# rfid_reader.net
KiCad netlist of a schematic drawn in Altium Designer
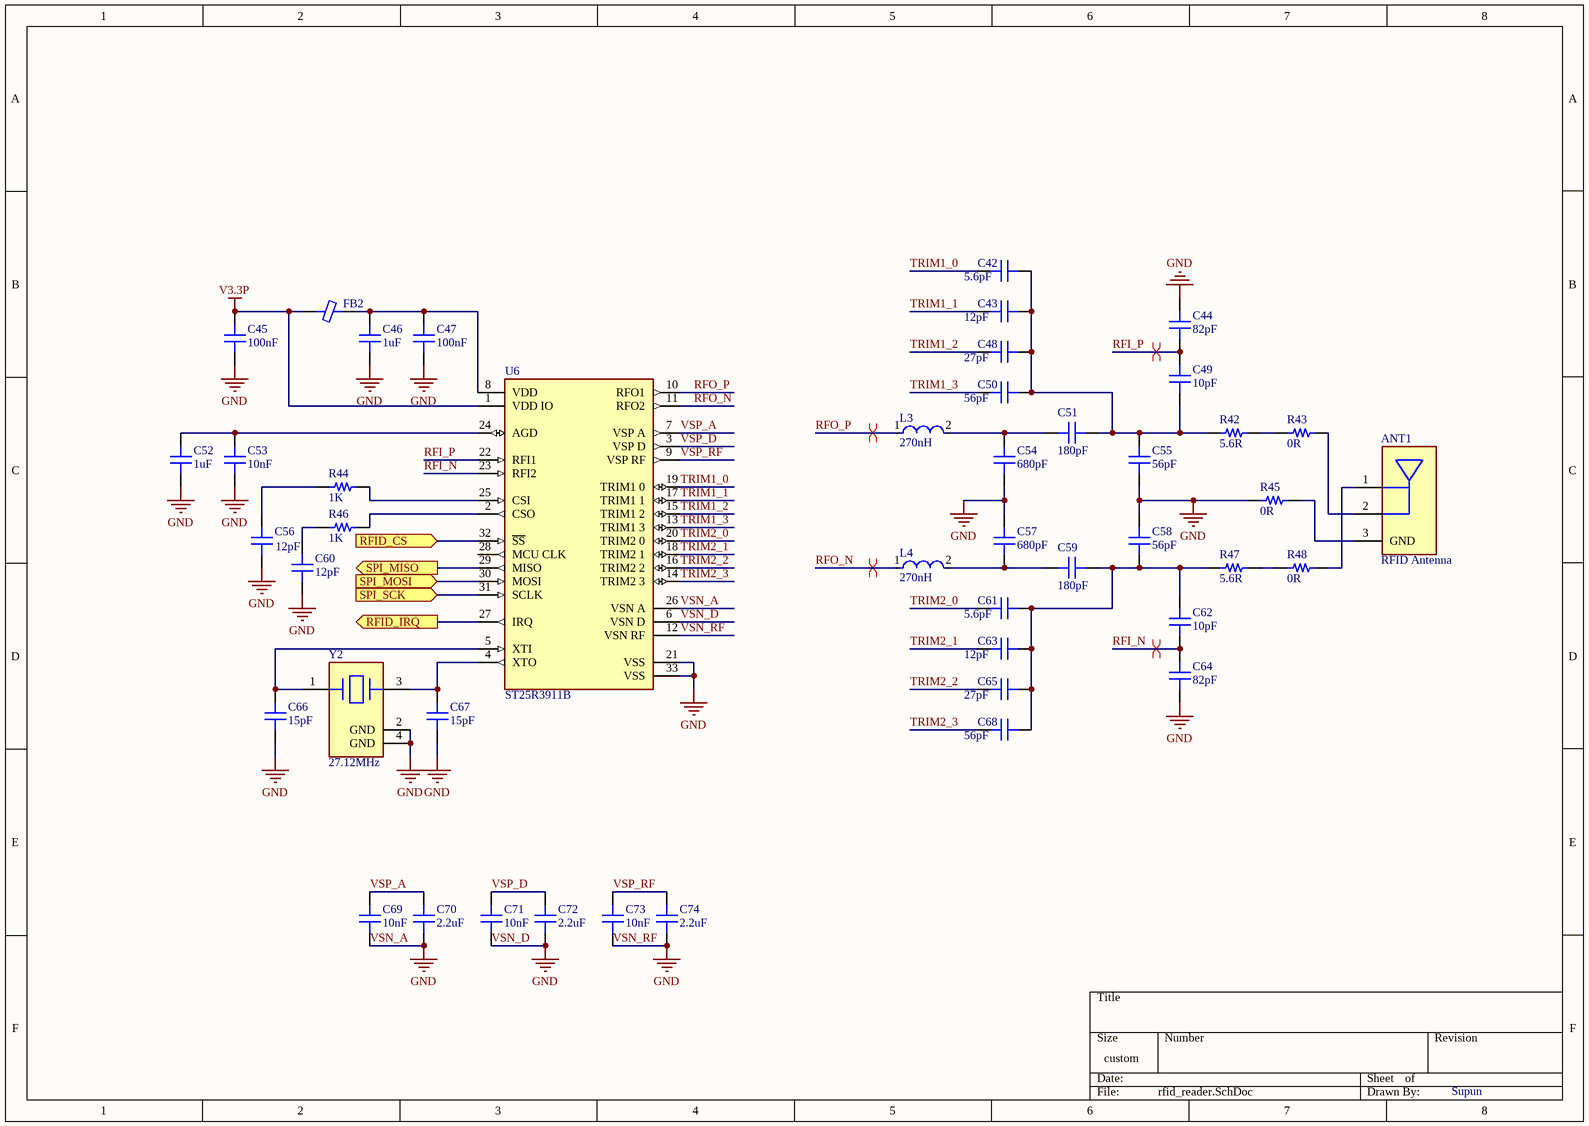
[diagram p0: rfid_reader.SchDoc]

(export (version "E")
  (design (tool "Eeschema 10.0.6"))
  (components
    (comp (ref "ANT1")
      (value "RFID Antenna")
      (footprint "RFID_Antenna")
      (description "13.56MHz RFID Antenna 926.04 nH")
      (fields (field (name "MF") "SAH"))
      (libsource (lib "Antenna") (part "Loop Antenna"))
    )
    (comp (ref "C42")
      (value "5.6pF")
      (footprint "CAP 0603_1608")
      (description "SMT Capacitor")
      (fields (field (name "MF") "Murata") (field (name "MP") "GRM1885C1H5R6BA01D"))
      (libsource (lib "Capacitor") (part "Capacitor"))
    )
    (comp (ref "C43")
      (value "12pF")
      (footprint "CAP 0603_1608")
      (description "SMT Capacitor")
      (fields (field (name "MF") "Murata") (field (name "MP") "GRM1885C1H120JA01J"))
      (libsource (lib "Capacitor") (part "Capacitor"))
    )
    (comp (ref "C44")
      (value "82pF")
      (footprint "CAP 0603_1608")
      (description "SMT Capacitor")
      (fields (field (name "MF") "Murata") (field (name "MP") "GRM1885C1H820GA01D"))
      (libsource (lib "Capacitor") (part "Capacitor"))
    )
    (comp (ref "C45")
      (value "100nF")
      (footprint "CAP 0603_1608")
      (description "SMT Capacitor")
      (fields (field (name "MF") "KEMET") (field (name "MP") "C0603C104K4PACTU"))
      (libsource (lib "Capacitor") (part "Capacitor"))
    )
    (comp (ref "C46")
      (value "1uF")
      (footprint "CAP 0603_1608")
      (description "SMT Capacitor")
      (fields (field (name "MF") "Samsung Electro-Mechanics") (field (name "MP") "CL10A105KO8NNND"))
      (libsource (lib "Capacitor") (part "Capacitor"))
    )
    (comp (ref "C47")
      (value "100nF")
      (footprint "CAP 0603_1608")
      (description "SMT Capacitor")
      (fields (field (name "MF") "KEMET") (field (name "MP") "C0603C104K4PACTU"))
      (libsource (lib "Capacitor") (part "Capacitor"))
    )
    (comp (ref "C48")
      (value "27pF")
      (footprint "CAP 0603_1608")
      (description "SMT Capacitor")
      (fields (field (name "MF") "Murata") (field (name "MP") "GRM1885C1H270JA01D"))
      (libsource (lib "Capacitor") (part "Capacitor"))
    )
    (comp (ref "C49")
      (value "10pF")
      (footprint "CAP 0603_1608")
      (description "SMT Capacitor")
      (fields (field (name "MF") "Murata") (field (name "MP") "GRM1885C1H100GA01D"))
      (libsource (lib "Capacitor") (part "Capacitor"))
    )
    (comp (ref "C50")
      (value "56pF")
      (footprint "CAP 0603_1608")
      (description "SMT Capacitor")
      (fields (field (name "MF") "Murata") (field (name "MP") "GRM1885C1H560JA01J"))
      (libsource (lib "Capacitor") (part "Capacitor"))
    )
    (comp (ref "C51")
      (value "180pF")
      (footprint "CAP 0603_1608")
      (description "SMT Capacitor")
      (fields (field (name "MF") "Murata") (field (name "MP") "GRM1885C1H181GA01D"))
      (libsource (lib "Capacitor") (part "Capacitor"))
    )
    (comp (ref "C52")
      (value "1uF")
      (footprint "CAP 0603_1608")
      (description "SMT Capacitor")
      (fields (field (name "MF") "Samsung Electro-Mechanics") (field (name "MP") "CL10A105KO8NNND"))
      (libsource (lib "Capacitor") (part "Capacitor"))
    )
    (comp (ref "C53")
      (value "10nF")
      (footprint "CAP 0603_1608")
      (description "SMT Capacitor")
      (fields (field (name "MF") "Samsung Electro-Mechanics") (field (name "MP") "CL10B103KA8WPNC"))
      (libsource (lib "Capacitor") (part "Capacitor"))
    )
    (comp (ref "C54")
      (value "680pF")
      (footprint "CAP 0603_1608")
      (description "SMT Capacitor")
      (fields (field (name "MF") "Murata") (field (name "MP") "GRM1885C1H681GA01D"))
      (libsource (lib "Capacitor") (part "Capacitor"))
    )
    (comp (ref "C55")
      (value "56pF")
      (footprint "CAP 0603_1608")
      (description "SMT Capacitor")
      (fields (field (name "MF") "Murata") (field (name "MP") "GRM1885C1H560JA01J"))
      (libsource (lib "Capacitor") (part "Capacitor"))
    )
    (comp (ref "C56")
      (value "12pF")
      (footprint "CAP 0603_1608")
      (description "SMT Capacitor")
      (fields (field (name "MF") "Murata") (field (name "MP") "GRM1885C1H120JA01J"))
      (libsource (lib "Capacitor") (part "Capacitor"))
    )
    (comp (ref "C57")
      (value "680pF")
      (footprint "CAP 0603_1608")
      (description "SMT Capacitor")
      (fields (field (name "MF") "Murata") (field (name "MP") "GRM1885C1H681GA01D"))
      (libsource (lib "Capacitor") (part "Capacitor"))
    )
    (comp (ref "C58")
      (value "56pF")
      (footprint "CAP 0603_1608")
      (description "SMT Capacitor")
      (fields (field (name "MF") "Murata") (field (name "MP") "GRM1885C1H560JA01J"))
      (libsource (lib "Capacitor") (part "Capacitor"))
    )
    (comp (ref "C59")
      (value "180pF")
      (footprint "CAP 0603_1608")
      (description "SMT Capacitor")
      (fields (field (name "MF") "Murata") (field (name "MP") "GRM1885C1H181GA01D"))
      (libsource (lib "Capacitor") (part "Capacitor"))
    )
    (comp (ref "C60")
      (value "12pF")
      (footprint "CAP 0603_1608")
      (description "SMT Capacitor")
      (fields (field (name "MF") "Murata") (field (name "MP") "GRM1885C1H120JA01J"))
      (libsource (lib "Capacitor") (part "Capacitor"))
    )
    (comp (ref "C61")
      (value "5.6pF")
      (footprint "CAP 0603_1608")
      (description "SMT Capacitor")
      (fields (field (name "MF") "Murata") (field (name "MP") "GRM1885C1H5R6BA01D"))
      (libsource (lib "Capacitor") (part "Capacitor"))
    )
    (comp (ref "C62")
      (value "10pF")
      (footprint "CAP 0603_1608")
      (description "SMT Capacitor")
      (fields (field (name "MF") "Murata") (field (name "MP") "GRM1885C1H100GA01D"))
      (libsource (lib "Capacitor") (part "Capacitor"))
    )
    (comp (ref "C63")
      (value "12pF")
      (footprint "CAP 0603_1608")
      (description "SMT Capacitor")
      (fields (field (name "MF") "Murata") (field (name "MP") "GRM1885C1H120JA01J"))
      (libsource (lib "Capacitor") (part "Capacitor"))
    )
    (comp (ref "C64")
      (value "82pF")
      (footprint "CAP 0603_1608")
      (description "SMT Capacitor")
      (fields (field (name "MF") "Murata") (field (name "MP") "GRM1885C1H820GA01D"))
      (libsource (lib "Capacitor") (part "Capacitor"))
    )
    (comp (ref "C65")
      (value "27pF")
      (footprint "CAP 0603_1608")
      (description "SMT Capacitor")
      (fields (field (name "MF") "Murata") (field (name "MP") "GRM1885C1H270JA01D"))
      (libsource (lib "Capacitor") (part "Capacitor"))
    )
    (comp (ref "C66")
      (value "15pF")
      (footprint "CAP 0603_1608")
      (description "SMT Capacitor")
      (fields (field (name "MF") "Murata") (field (name "MP") "GRM1885C1H150JA01J"))
      (libsource (lib "Capacitor") (part "Capacitor"))
    )
    (comp (ref "C67")
      (value "15pF")
      (footprint "CAP 0603_1608")
      (description "SMT Capacitor")
      (fields (field (name "MF") "Murata") (field (name "MP") "GRM1885C1H150JA01J"))
      (libsource (lib "Capacitor") (part "Capacitor"))
    )
    (comp (ref "C68")
      (value "56pF")
      (footprint "CAP 0603_1608")
      (description "SMT Capacitor")
      (fields (field (name "MF") "Murata") (field (name "MP") "GRM1885C1H560JA01J"))
      (libsource (lib "Capacitor") (part "Capacitor"))
    )
    (comp (ref "C69")
      (value "10nF")
      (footprint "CAP 0603_1608")
      (description "SMT Capacitor")
      (fields (field (name "MF") "Samsung Electro-Mechanics") (field (name "MP") "CL10B103KA8WPNC"))
      (libsource (lib "Capacitor") (part "Capacitor"))
    )
    (comp (ref "C70")
      (value "2.2uF")
      (footprint "CAP 0603_1608")
      (description "SMT Capacitor")
      (fields (field (name "MF") "Samsung Electro-Mechanics") (field (name "MP") "CL10A225KP8NNNC"))
      (libsource (lib "Capacitor") (part "Capacitor"))
    )
    (comp (ref "C71")
      (value "10nF")
      (footprint "CAP 0603_1608")
      (description "SMT Capacitor")
      (fields (field (name "MF") "Samsung Electro-Mechanics") (field (name "MP") "CL10B103KA8WPNC"))
      (libsource (lib "Capacitor") (part "Capacitor"))
    )
    (comp (ref "C72")
      (value "2.2uF")
      (footprint "CAP 0603_1608")
      (description "SMT Capacitor")
      (fields (field (name "MF") "Samsung Electro-Mechanics") (field (name "MP") "CL10A225KP8NNNC"))
      (libsource (lib "Capacitor") (part "Capacitor"))
    )
    (comp (ref "C73")
      (value "10nF")
      (footprint "CAP 0603_1608")
      (description "SMT Capacitor")
      (fields (field (name "MF") "Samsung Electro-Mechanics") (field (name "MP") "CL10B103KA8WPNC"))
      (libsource (lib "Capacitor") (part "Capacitor"))
    )
    (comp (ref "C74")
      (value "2.2uF")
      (footprint "CAP 0603_1608")
      (description "SMT Capacitor")
      (fields (field (name "MF") "Samsung Electro-Mechanics") (field (name "MP") "CL10A225KP8NNNC"))
      (libsource (lib "Capacitor") (part "Capacitor"))
    )
    (comp (ref "FB2")
      (value "~")
      (footprint "Murata_BLM18-0_15-t0_8_MFG")
      (description "SMT Ferrite Chip")
      (fields (field (name "MF") "Murata Electronics") (field (name "MP") "BLM18AG331SN1D"))
      (libsource (lib "Passive") (part "Ferrite Chip"))
    )
    (comp (ref "L3")
      (value "270nH")
      (footprint "IND 0603_1608")
      (description "Fixed Inductors 2.2uH 20% High Temp AEC-Q200")
      (fields (field (name "MF") "Murata") (field (name "MP") "LQW18ANR27G80D"))
      (libsource (lib "Inductor") (part "Inductor_sm"))
    )
    (comp (ref "L4")
      (value "270nH")
      (footprint "IND 0603_1608")
      (description "Fixed Inductors 2.2uH 20% High Temp AEC-Q200")
      (fields (field (name "MF") "Murata") (field (name "MP") "LQW18ANR27G80D"))
      (libsource (lib "Inductor") (part "Inductor_sm"))
    )
    (comp (ref "R42")
      (value "5.6R")
      (footprint "RES 0603_1608")
      (description "SMT Resistor")
      (fields (field (name "MF") "Vishay") (field (name "MP") "CRCW06035R62FKEA"))
      (libsource (lib "Resistor") (part "Resistor"))
    )
    (comp (ref "R43")
      (value "0R")
      (footprint "RES 0603_1608")
      (description "SMT Resistor")
      (fields (field (name "MF") "Vishay") (field (name "MP") "RCC06030000Z0EA"))
      (libsource (lib "Resistor") (part "Resistor"))
    )
    (comp (ref "R44")
      (value "1K")
      (footprint "RES 0603_1608")
      (description "SMT Resistor")
      (fields (field (name "MF") "Vishay") (field (name "MP") "CRCW06031K00FKEAC"))
      (libsource (lib "Resistor") (part "Resistor"))
    )
    (comp (ref "R45")
      (value "0R")
      (footprint "RES 0603_1608")
      (description "SMT Resistor")
      (fields (field (name "MF") "Vishay") (field (name "MP") "RCC06030000Z0EA"))
      (libsource (lib "Resistor") (part "Resistor"))
    )
    (comp (ref "R46")
      (value "1K")
      (footprint "RES 0603_1608")
      (description "SMT Resistor")
      (fields (field (name "MF") "Vishay") (field (name "MP") "CRCW06031K00FKEAC"))
      (libsource (lib "Resistor") (part "Resistor"))
    )
    (comp (ref "R47")
      (value "5.6R")
      (footprint "RES 0603_1608")
      (description "SMT Resistor")
      (fields (field (name "MF") "Vishay") (field (name "MP") "CRCW06035R62FKEA"))
      (libsource (lib "Resistor") (part "Resistor"))
    )
    (comp (ref "R48")
      (value "0R")
      (footprint "RES 0603_1608")
      (description "SMT Resistor")
      (fields (field (name "MF") "Vishay") (field (name "MP") "RCC06030000Z0EA"))
      (libsource (lib "Resistor") (part "Resistor"))
    )
    (comp (ref "U6")
      (value "ST25R3911B")
      (footprint "ST_QFN32L-7376875_MFG")
      (description "IC RFID Reader IC 13.56MHz ISO 14443, NFC SPI 2.4 V ~ 5.5 V 32-VFQFN Exposed Pad")
      (fields
        (field (name "MF") "STMicroelectronics")
        (field (name "MOUSER PART NUMBER") "511-ST25R3911B-AQFT")
      )
      (libsource (lib "RfidScanner") (part "ST25R3911B"))
    )
    (comp (ref "Y2")
      (value "27.12MHz")
      (footprint "ABRACON ABM8G")
      (description "Crystals AEC-Q200 CRYSTAL 4pin SMD")
      (fields (field (name "MF") "ECS") (field (name "MP") "ECS-271.2-8-33-RWY-TR"))
      (libsource (lib "Crystal") (part "Crystal"))
    )
  )
  (nets
    (net (code "1") (name "/RFID_CS") (class "Default")
      (node (ref "U6") (pin "32") (pinfunction "~{SS}_32") (pintype "input"))
    )
    (net (code "2") (name "/RFID_IRQ") (class "Default")
      (node (ref "U6") (pin "27") (pinfunction "IRQ_27") (pintype "output"))
    )
    (net (code "3") (name "/RFI_N") (class "Default")
      (node (ref "C62") (pin "2") (pinfunction "2_2") (pintype "passive"))
      (node (ref "C64") (pin "1") (pinfunction "1_1") (pintype "passive"))
      (node (ref "U6") (pin "23") (pinfunction "RFI2_23") (pintype "input"))
    )
    (net (code "4") (name "/RFI_P") (class "Default")
      (node (ref "C44") (pin "2") (pinfunction "2_2") (pintype "passive"))
      (node (ref "C49") (pin "1") (pinfunction "1_1") (pintype "passive"))
      (node (ref "U6") (pin "22") (pinfunction "RFI1_22") (pintype "input"))
    )
    (net (code "5") (name "/RFO_N") (class "Default")
      (node (ref "L4") (pin "1") (pinfunction "1_1") (pintype "passive"))
      (node (ref "U6") (pin "11") (pinfunction "RFO2_11") (pintype "output"))
    )
    (net (code "6") (name "/RFO_P") (class "Default")
      (node (ref "L3") (pin "1") (pinfunction "1_1") (pintype "passive"))
      (node (ref "U6") (pin "10") (pinfunction "RFO1_10") (pintype "output"))
    )
    (net (code "7") (name "/SPI_MISO") (class "Default")
      (node (ref "U6") (pin "29") (pinfunction "MISO_29") (pintype "output"))
    )
    (net (code "8") (name "/SPI_MOSI") (class "Default")
      (node (ref "U6") (pin "30") (pinfunction "MOSI_30") (pintype "input"))
    )
    (net (code "9") (name "/SPI_SCK") (class "Default")
      (node (ref "U6") (pin "31") (pinfunction "SCLK_31") (pintype "input"))
    )
    (net (code "10") (name "/TRIM1_0") (class "Default")
      (node (ref "C42") (pin "1") (pinfunction "1_1") (pintype "passive"))
      (node (ref "U6") (pin "19") (pinfunction "TRIM1_0_19") (pintype "bidirectional"))
    )
    (net (code "11") (name "/TRIM1_1") (class "Default")
      (node (ref "C43") (pin "1") (pinfunction "1_1") (pintype "passive"))
      (node (ref "U6") (pin "17") (pinfunction "TRIM1_1_17") (pintype "bidirectional"))
    )
    (net (code "12") (name "/TRIM1_2") (class "Default")
      (node (ref "C48") (pin "1") (pinfunction "1_1") (pintype "passive"))
      (node (ref "U6") (pin "15") (pinfunction "TRIM1_2_15") (pintype "bidirectional"))
    )
    (net (code "13") (name "/TRIM1_3") (class "Default")
      (node (ref "C50") (pin "1") (pinfunction "1_1") (pintype "passive"))
      (node (ref "U6") (pin "13") (pinfunction "TRIM1_3_13") (pintype "bidirectional"))
    )
    (net (code "14") (name "/TRIM2_0") (class "Default")
      (node (ref "C61") (pin "1") (pinfunction "1_1") (pintype "passive"))
      (node (ref "U6") (pin "20") (pinfunction "TRIM2_0_20") (pintype "bidirectional"))
    )
    (net (code "15") (name "/TRIM2_1") (class "Default")
      (node (ref "C63") (pin "1") (pinfunction "1_1") (pintype "passive"))
      (node (ref "U6") (pin "18") (pinfunction "TRIM2_1_18") (pintype "bidirectional"))
    )
    (net (code "16") (name "/TRIM2_2") (class "Default")
      (node (ref "C65") (pin "1") (pinfunction "1_1") (pintype "passive"))
      (node (ref "U6") (pin "16") (pinfunction "TRIM2_2_16") (pintype "bidirectional"))
    )
    (net (code "17") (name "/TRIM2_3") (class "Default")
      (node (ref "C68") (pin "1") (pinfunction "1_1") (pintype "passive"))
      (node (ref "U6") (pin "14") (pinfunction "TRIM2_3_14") (pintype "bidirectional"))
    )
    (net (code "18") (name "/VSP_A") (class "Default")
      (node (ref "C69") (pin "1") (pinfunction "1_1") (pintype "passive"))
      (node (ref "C70") (pin "1") (pinfunction "1_1") (pintype "passive"))
      (node (ref "U6") (pin "7") (pinfunction "VSP_A_7") (pintype "output"))
    )
    (net (code "19") (name "/VSP_D") (class "Default")
      (node (ref "C71") (pin "1") (pinfunction "1_1") (pintype "passive"))
      (node (ref "C72") (pin "1") (pinfunction "1_1") (pintype "passive"))
      (node (ref "U6") (pin "3") (pinfunction "VSP_D_3") (pintype "output"))
    )
    (net (code "20") (name "/VSP_RF") (class "Default")
      (node (ref "C73") (pin "1") (pinfunction "1_1") (pintype "passive"))
      (node (ref "C74") (pin "1") (pinfunction "1_1") (pintype "passive"))
      (node (ref "U6") (pin "9") (pinfunction "VSP_RF_9") (pintype "output"))
    )
    (net (code "21") (name "GND") (class "Default")
      (node (ref "C44") (pin "1") (pinfunction "1_1") (pintype "passive"))
      (node (ref "C45") (pin "2") (pinfunction "2_2") (pintype "passive"))
      (node (ref "C46") (pin "2") (pinfunction "2_2") (pintype "passive"))
      (node (ref "C47") (pin "2") (pinfunction "2_2") (pintype "passive"))
      (node (ref "C52") (pin "2") (pinfunction "2_2") (pintype "passive"))
      (node (ref "C53") (pin "2") (pinfunction "2_2") (pintype "passive"))
      (node (ref "C54") (pin "1") (pinfunction "1_1") (pintype "passive"))
      (node (ref "C55") (pin "1") (pinfunction "1_1") (pintype "passive"))
      (node (ref "C56") (pin "1") (pinfunction "1_1") (pintype "passive"))
      (node (ref "C57") (pin "2") (pinfunction "2_2") (pintype "passive"))
      (node (ref "C58") (pin "2") (pinfunction "2_2") (pintype "passive"))
      (node (ref "C60") (pin "1") (pinfunction "1_1") (pintype "passive"))
      (node (ref "C64") (pin "2") (pinfunction "2_2") (pintype "passive"))
      (node (ref "C66") (pin "2") (pinfunction "2_2") (pintype "passive"))
      (node (ref "C67") (pin "2") (pinfunction "2_2") (pintype "passive"))
      (node (ref "C69") (pin "2") (pinfunction "2_2") (pintype "passive"))
      (node (ref "C70") (pin "2") (pinfunction "2_2") (pintype "passive"))
      (node (ref "C71") (pin "2") (pinfunction "2_2") (pintype "passive"))
      (node (ref "C72") (pin "2") (pinfunction "2_2") (pintype "passive"))
      (node (ref "C73") (pin "2") (pinfunction "2_2") (pintype "passive"))
      (node (ref "C74") (pin "2") (pinfunction "2_2") (pintype "passive"))
      (node (ref "R45") (pin "1") (pinfunction "1_1") (pintype "passive"))
      (node (ref "U6") (pin "12") (pinfunction "VSN_RF_12") (pintype "power_in"))
      (node (ref "U6") (pin "21") (pinfunction "VSS_21") (pintype "power_in"))
      (node (ref "U6") (pin "26") (pinfunction "VSN_A_26") (pintype "power_in"))
      (node (ref "U6") (pin "33") (pinfunction "VSS_33") (pintype "power_in"))
      (node (ref "U6") (pin "6") (pinfunction "VSN_D_6") (pintype "power_in"))
      (node (ref "Y2") (pin "2") (pinfunction "GND_2") (pintype "power_in"))
      (node (ref "Y2") (pin "4") (pinfunction "GND_4") (pintype "power_in"))
    )
    (net (code "22") (name "Net-(ANT1-GND)") (class "Default")
      (node (ref "ANT1") (pin "3") (pinfunction "GND_3") (pintype "passive"))
      (node (ref "R45") (pin "2") (pinfunction "2_2") (pintype "passive"))
    )
    (net (code "23") (name "Net-(ANT1-Pad1)") (class "Default")
      (node (ref "ANT1") (pin "1") (pinfunction "1_1") (pintype "passive"))
      (node (ref "R48") (pin "2") (pinfunction "2_2") (pintype "passive"))
    )
    (net (code "24") (name "Net-(ANT1-Pad2)") (class "Default")
      (node (ref "ANT1") (pin "2") (pinfunction "2_2") (pintype "passive"))
      (node (ref "R43") (pin "2") (pinfunction "2_2") (pintype "passive"))
    )
    (net (code "25") (name "Net-(C42-Pad2)") (class "Default")
      (node (ref "C42") (pin "2") (pinfunction "2_2") (pintype "passive"))
      (node (ref "C43") (pin "2") (pinfunction "2_2") (pintype "passive"))
      (node (ref "C48") (pin "2") (pinfunction "2_2") (pintype "passive"))
      (node (ref "C49") (pin "2") (pinfunction "2_2") (pintype "passive"))
      (node (ref "C50") (pin "2") (pinfunction "2_2") (pintype "passive"))
      (node (ref "C51") (pin "1") (pinfunction "1_1") (pintype "passive"))
      (node (ref "C55") (pin "2") (pinfunction "2_2") (pintype "passive"))
      (node (ref "R42") (pin "1") (pinfunction "1_1") (pintype "passive"))
    )
    (net (code "26") (name "Net-(C51-Pad2)") (class "Default")
      (node (ref "C51") (pin "2") (pinfunction "2_2") (pintype "passive"))
      (node (ref "C54") (pin "2") (pinfunction "2_2") (pintype "passive"))
      (node (ref "L3") (pin "2") (pinfunction "2_2") (pintype "passive"))
    )
    (net (code "27") (name "Net-(C56-Pad2)") (class "Default")
      (node (ref "C56") (pin "2") (pinfunction "2_2") (pintype "passive"))
      (node (ref "R44") (pin "1") (pinfunction "1_1") (pintype "passive"))
    )
    (net (code "28") (name "Net-(C57-Pad1)") (class "Default")
      (node (ref "C57") (pin "1") (pinfunction "1_1") (pintype "passive"))
      (node (ref "C59") (pin "2") (pinfunction "2_2") (pintype "passive"))
      (node (ref "L4") (pin "2") (pinfunction "2_2") (pintype "passive"))
    )
    (net (code "29") (name "Net-(C58-Pad1)") (class "Default")
      (node (ref "C58") (pin "1") (pinfunction "1_1") (pintype "passive"))
      (node (ref "C59") (pin "1") (pinfunction "1_1") (pintype "passive"))
      (node (ref "C61") (pin "2") (pinfunction "2_2") (pintype "passive"))
      (node (ref "C62") (pin "1") (pinfunction "1_1") (pintype "passive"))
      (node (ref "C63") (pin "2") (pinfunction "2_2") (pintype "passive"))
      (node (ref "C65") (pin "2") (pinfunction "2_2") (pintype "passive"))
      (node (ref "C68") (pin "2") (pinfunction "2_2") (pintype "passive"))
      (node (ref "R47") (pin "1") (pinfunction "1_1") (pintype "passive"))
    )
    (net (code "30") (name "Net-(C60-Pad2)") (class "Default")
      (node (ref "C60") (pin "2") (pinfunction "2_2") (pintype "passive"))
      (node (ref "R46") (pin "1") (pinfunction "1_1") (pintype "passive"))
    )
    (net (code "31") (name "Net-(R42-Pad2)") (class "Default")
      (node (ref "R42") (pin "2") (pinfunction "2_2") (pintype "passive"))
      (node (ref "R43") (pin "1") (pinfunction "1_1") (pintype "passive"))
    )
    (net (code "32") (name "Net-(R47-Pad2)") (class "Default")
      (node (ref "R47") (pin "2") (pinfunction "2_2") (pintype "passive"))
      (node (ref "R48") (pin "1") (pinfunction "1_1") (pintype "passive"))
    )
    (net (code "33") (name "Net-(U6-AGD)") (class "Default")
      (node (ref "C52") (pin "1") (pinfunction "1_1") (pintype "passive"))
      (node (ref "C53") (pin "1") (pinfunction "1_1") (pintype "passive"))
      (node (ref "U6") (pin "24") (pinfunction "AGD_24") (pintype "bidirectional"))
    )
    (net (code "34") (name "Net-(U6-CSI)") (class "Default")
      (node (ref "R44") (pin "2") (pinfunction "2_2") (pintype "passive"))
      (node (ref "U6") (pin "25") (pinfunction "CSI_25") (pintype "input"))
    )
    (net (code "35") (name "Net-(U6-CSO)") (class "Default")
      (node (ref "R46") (pin "2") (pinfunction "2_2") (pintype "passive"))
      (node (ref "U6") (pin "2") (pinfunction "CSO_2") (pintype "output"))
    )
    (net (code "36") (name "Net-(U6-VDD)") (class "Default")
      (node (ref "C46") (pin "1") (pinfunction "1_1") (pintype "passive"))
      (node (ref "C47") (pin "1") (pinfunction "1_1") (pintype "passive"))
      (node (ref "FB2") (pin "2") (pinfunction "2_2") (pintype "passive"))
      (node (ref "U6") (pin "8") (pinfunction "VDD_8") (pintype "power_in"))
    )
    (net (code "37") (name "Net-(U6-XTI)") (class "Default")
      (node (ref "C66") (pin "1") (pinfunction "1_1") (pintype "passive"))
      (node (ref "U6") (pin "5") (pinfunction "XTI_5") (pintype "input"))
      (node (ref "Y2") (pin "1") (pinfunction "1_1") (pintype "passive"))
    )
    (net (code "38") (name "Net-(U6-XTO)") (class "Default")
      (node (ref "C67") (pin "1") (pinfunction "1_1") (pintype "passive"))
      (node (ref "U6") (pin "4") (pinfunction "XTO_4") (pintype "output"))
      (node (ref "Y2") (pin "3") (pinfunction "3_3") (pintype "passive"))
    )
    (net (code "39") (name "V3.3P") (class "Default")
      (node (ref "C45") (pin "1") (pinfunction "1_1") (pintype "passive"))
      (node (ref "FB2") (pin "1") (pinfunction "1_1") (pintype "passive"))
      (node (ref "U6") (pin "1") (pinfunction "VDD_IO_1") (pintype "power_in"))
    )
    (net (code "40") (name "unconnected-(U6-MCU_CLK-Pad28)") (class "Default")
      (node (ref "U6") (pin "28") (pinfunction "MCU_CLK_28") (pintype "output"))
    )
  )
)
